# Master.net
KiCad netlist of a schematic drawn in Altium Designer
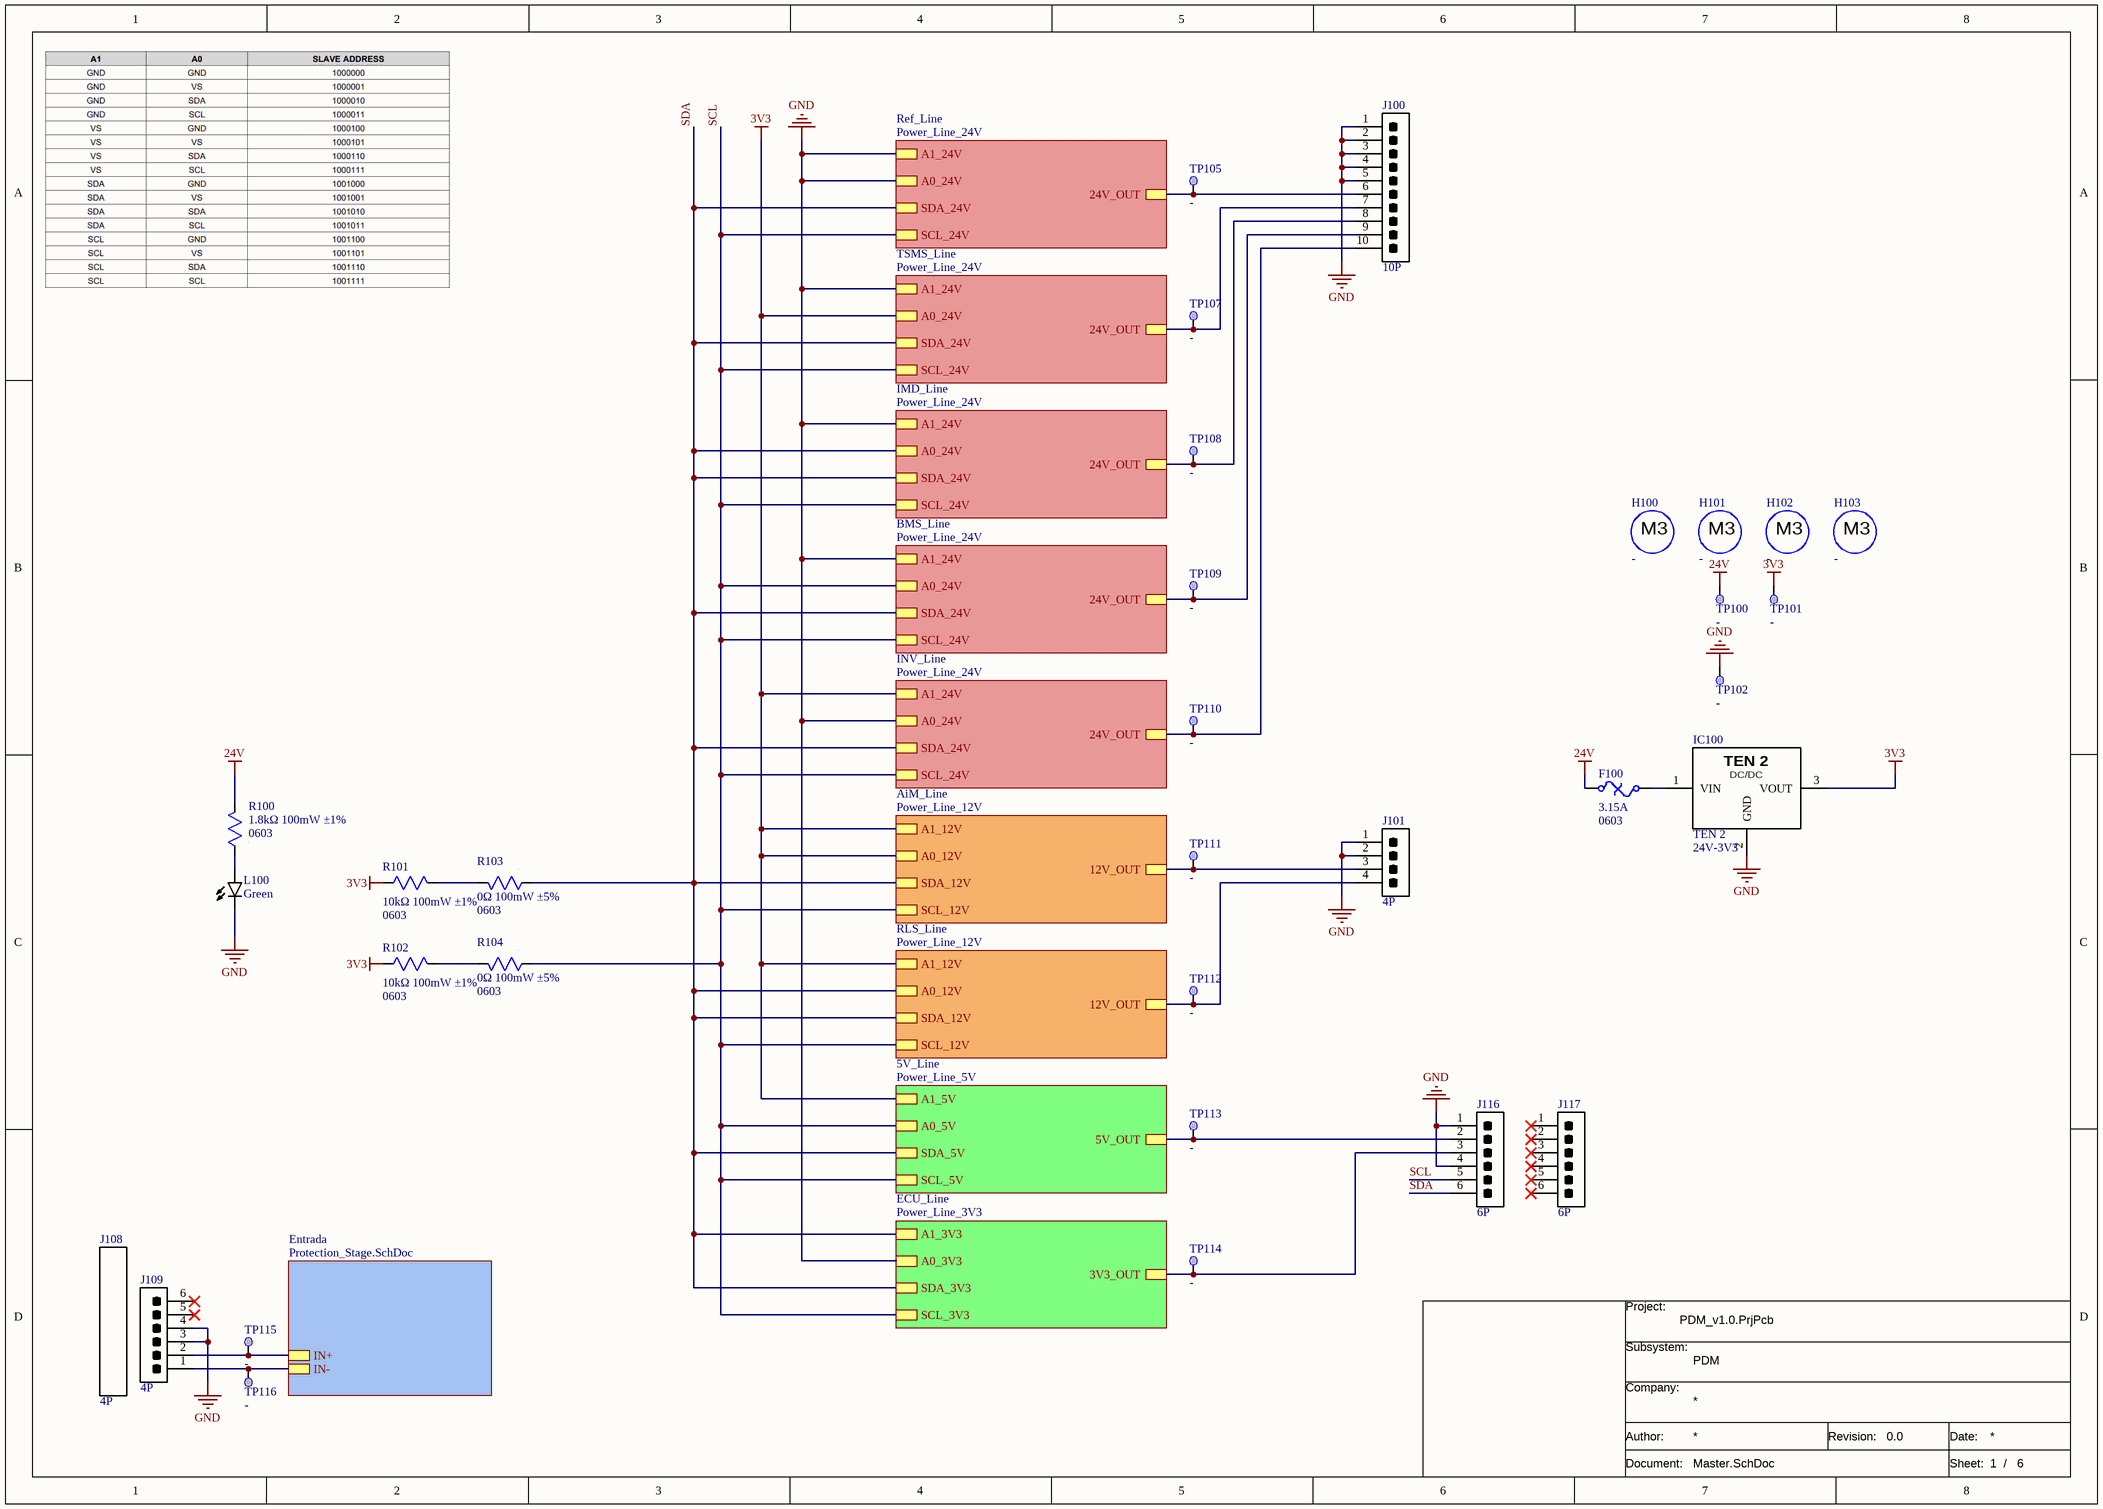
[diagram p0: Master.SchDoc]

(export (version "E")
  (design (tool "Eeschema 10.0.6"))
  (components
    (comp (ref "F100")
      (value "3.15A")
      (footprint "FUSE SMD 0603")
      (description "Surface Mount Fuses 3.15A Slow Blow 0603 SinglFuse")
      (fields
        (field (name "PACKAGE") "0603")
        (field (name "MPN") "SF-0603S315-2")
        (field (name "MANUFACTURER") "Bourns")
      )
      (libsource (lib "eUSR_Database") (part "FUSE"))
    )
    (comp (ref "H100")
      (value "-")
      (footprint "M3")
      (description "M3 Screw")
      (fields (field (name "Comment") "SCREW M3"))
      (libsource (lib "eUSR_Database") (part "SCREW M3"))
    )
    (comp (ref "H101")
      (value "-")
      (footprint "M3")
      (description "M3 Screw")
      (fields (field (name "Comment") "SCREW M3"))
      (libsource (lib "eUSR_Database") (part "SCREW M3"))
    )
    (comp (ref "H102")
      (value "-")
      (footprint "M3")
      (description "M3 Screw")
      (fields (field (name "Comment") "SCREW M3"))
      (libsource (lib "eUSR_Database") (part "SCREW M3"))
    )
    (comp (ref "H103")
      (value "-")
      (footprint "M3")
      (description "M3 Screw")
      (fields (field (name "Comment") "SCREW M3"))
      (libsource (lib "eUSR_Database") (part "SCREW M3"))
    )
    (comp (ref "IC100")
      (value "TEN 2")
      (footprint "TEN 2")
      (description "Convertidores DC/DC para montaje pasante 4.75-36Vin 3.3V 2A switching regulator")
      (fields
        (field (name "ALTIUM_VALUE") "24V-3V3")
        (field (name "MPN") "TSR 2-2433")
        (field (name "MANUFACTURER") "TRACO Power")
      )
      (libsource (lib "eUSR_Database") (part "TEN 2"))
    )
    (comp (ref "J100")
      (value "10P")
      (footprint "657010240101")
      (fields
        (field (name "MPN") "657010240101")
        (field (name "MANUFACTURER") "Wurth Elektronik")
        (field (name "Comment") "CONN 10P")
      )
      (libsource (lib "eUSR_Database") (part "CONN 10P"))
    )
    (comp (ref "J101")
      (value "4P")
      (footprint "657004240101")
      (fields
        (field (name "MPN") "657004240101")
        (field (name "MANUFACTURER") "Wurth Elektronik")
        (field (name "Comment") "CONN 4P")
      )
      (libsource (lib "eUSR_Database") (part "CONN 4P"))
    )
    (comp (ref "J108")
      (value "4P")
      (footprint "657004150201")
      (description "Receptacle Single Row")
      (fields (field (name "MPN") "657004150201") (field (name "MANUFACTURER") "Wurth Elektronik"))
      (libsource (lib "eUSR_Database") (part "AEREO"))
    )
    (comp (ref "J109")
      (value "4P")
      (footprint "657004140101")
      (description "WR-MPC5 Male Header Single Row")
      (fields (field (name "MPN") "657004140101") (field (name "MANUFACTURER") "Wurth Elektronik"))
      (libsource (lib "eUSR_Database") (part "CONN 6P"))
    )
    (comp (ref "J116")
      (value "6P")
      (footprint "HEADERS_MALE_6P_2.54MM")
      (description "Pin Header 6 Position 2.54mm Pitch Single Row Through Hole -55℃~+105℃")
      (fields (field (name "MPN") "2541WV-06P") (field (name "MANUFACTURER") "HanElectricity"))
      (libsource (lib "") (part "CONN 6P_1"))
    )
    (comp (ref "J117")
      (value "6P")
      (footprint "HEADERS_MALE_6P_2.54MM")
      (description "Pin Header 6 Position 2.54mm Pitch Single Row Through Hole -55℃~+105℃")
      (fields (field (name "MPN") "2541WV-06P") (field (name "MANUFACTURER") "HanElectricity"))
      (libsource (lib "") (part "CONN 6P_1"))
    )
    (comp (ref "L100")
      (value "Green")
      (footprint "LED SMD 0603")
      (description "LED de un solo color Green 525nm 1400mcd 2.85V 73deg 0603")
      (fields (field (name "MPN") "VLMTG1400-GS08") (field (name "MANUFACTURER") "Vishay Semiconductors"))
      (libsource (lib "eUSR_Database") (part "LED WHITE"))
    )
    (comp (ref "R100")
      (value "1.8kΩ 100mW ±1%")
      (footprint "RES SMD 0603")
      (description "Resistores de película gruesa - SMD WRIS-RSKS 1.8 kOhms 1 % 0.1 W 0603 AEC-Q200")
      (fields
        (field (name "PACKAGE") "0603")
        (field (name "MPN") "560112116032")
        (field (name "MANUFACTURER") "Wurth Elektronik")
      )
      (libsource (lib "eUSR_Database") (part "RES"))
    )
    (comp (ref "R101")
      (value "10kΩ 100mW ±1%")
      (footprint "RES SMD 0603")
      (description "Resistores de película gruesa - SMD WRIS-RSKS 10 kOhms 1 % 0.1 W 0603 AEC-Q200")
      (fields
        (field (name "PACKAGE") "0603")
        (field (name "MPN") "560112116005")
        (field (name "MANUFACTURER") "Wurth Elektronik")
      )
      (libsource (lib "eUSR_Database") (part "RES"))
    )
    (comp (ref "R102")
      (value "10kΩ 100mW ±1%")
      (footprint "RES SMD 0603")
      (description "Resistores de película gruesa - SMD WRIS-RSKS 10 kOhms 1 % 0.1 W 0603 AEC-Q200")
      (fields
        (field (name "PACKAGE") "0603")
        (field (name "MPN") "560112116005")
        (field (name "MANUFACTURER") "Wurth Elektronik")
      )
      (libsource (lib "eUSR_Database") (part "RES"))
    )
    (comp (ref "R103")
      (value "0Ω 100mW ±5%")
      (footprint "RES SMD 0603")
      (description "Resistores de película gruesa - SMD WRIS-RSKS <0.05 Ohms 0.1 W Jumper 0603 AEC-Q200")
      (fields
        (field (name "PACKAGE") "0603")
        (field (name "MPN") "560112116001")
        (field (name "MANUFACTURER") "Wurth Elektronik")
      )
      (libsource (lib "eUSR_Database") (part "RES"))
    )
    (comp (ref "R104")
      (value "0Ω 100mW ±5%")
      (footprint "RES SMD 0603")
      (description "Resistores de película gruesa - SMD WRIS-RSKS <0.05 Ohms 0.1 W Jumper 0603 AEC-Q200")
      (fields
        (field (name "PACKAGE") "0603")
        (field (name "MPN") "560112116001")
        (field (name "MANUFACTURER") "Wurth Elektronik")
      )
      (libsource (lib "eUSR_Database") (part "RES"))
    )
    (comp (ref "TP100")
      (value "-")
      (footprint "TP_SMD_1MM")
      (description "Test Point")
      (libsource (lib "") (part "TP1mm_1"))
    )
    (comp (ref "TP101")
      (value "-")
      (footprint "TP_SMD_1MM")
      (description "Test Point")
      (libsource (lib "") (part "TP1mm_1"))
    )
    (comp (ref "TP102")
      (value "-")
      (footprint "TP_SMD_1MM")
      (description "Test Point")
      (libsource (lib "") (part "TP1mm_1"))
    )
    (comp (ref "TP105")
      (value "-")
      (footprint "TP_SMD_1MM")
      (description "Test Point")
      (libsource (lib "eUSR_Database") (part "TP1mm"))
    )
    (comp (ref "TP107")
      (value "-")
      (footprint "TP_SMD_1MM")
      (description "Test Point")
      (libsource (lib "eUSR_Database") (part "TP1mm"))
    )
    (comp (ref "TP108")
      (value "-")
      (footprint "TP_SMD_1MM")
      (description "Test Point")
      (libsource (lib "eUSR_Database") (part "TP1mm"))
    )
    (comp (ref "TP109")
      (value "-")
      (footprint "TP_SMD_1MM")
      (description "Test Point")
      (libsource (lib "eUSR_Database") (part "TP1mm"))
    )
    (comp (ref "TP110")
      (value "-")
      (footprint "TP_SMD_1MM")
      (description "Test Point")
      (libsource (lib "eUSR_Database") (part "TP1mm"))
    )
    (comp (ref "TP111")
      (value "-")
      (footprint "TP_SMD_1MM")
      (description "Test Point")
      (libsource (lib "eUSR_Database") (part "TP1mm"))
    )
    (comp (ref "TP112")
      (value "-")
      (footprint "TP_SMD_1MM")
      (description "Test Point")
      (libsource (lib "eUSR_Database") (part "TP1mm"))
    )
    (comp (ref "TP113")
      (value "-")
      (footprint "TP_SMD_1MM")
      (description "Test Point")
      (libsource (lib "eUSR_Database") (part "TP1mm"))
    )
    (comp (ref "TP114")
      (value "-")
      (footprint "TP_SMD_1MM")
      (description "Test Point")
      (libsource (lib "eUSR_Database") (part "TP1mm"))
    )
    (comp (ref "TP115")
      (value "-")
      (footprint "TP_SMD_1MM")
      (description "Test Point")
      (libsource (lib "eUSR_Database") (part "TP1mm"))
    )
    (comp (ref "TP116")
      (value "-")
      (footprint "TP_SMD_1MM")
      (description "Test Point")
      (libsource (lib "") (part "TP1mm_1"))
    )
  )
  (nets
    (net (code "1") (name "/3V3_OUT") (class "Default")
      (node (ref "J116") (pin "3") (pinfunction "3_3") (pintype "passive"))
      (node (ref "TP114") (pin "1") (pinfunction "1_1") (pintype "passive"))
    )
    (net (code "2") (name "/5V_OUT") (class "Default")
      (node (ref "J116") (pin "2") (pinfunction "2_2") (pintype "passive"))
      (node (ref "TP113") (pin "1") (pinfunction "1_1") (pintype "passive"))
    )
    (net (code "3") (name "/12V_OUT") (class "Default")
      (node (ref "J101") (pin "4") (pinfunction "4_4") (pintype "passive"))
      (node (ref "TP112") (pin "1") (pinfunction "1_1") (pintype "passive"))
    )
    (net (code "4") (name "/12V_OUT_1") (class "Default")
      (node (ref "J101") (pin "3") (pinfunction "3_3") (pintype "passive"))
      (node (ref "TP111") (pin "1") (pinfunction "1_1") (pintype "passive"))
    )
    (net (code "5") (name "/24V_OUT") (class "Default")
      (node (ref "J100") (pin "6") (pinfunction "6_6") (pintype "passive"))
      (node (ref "TP105") (pin "1") (pinfunction "1_1") (pintype "passive"))
    )
    (net (code "6") (name "/24V_OUT_1") (class "Default")
      (node (ref "J100") (pin "10") (pinfunction "10_10") (pintype "passive"))
      (node (ref "TP110") (pin "1") (pinfunction "1_1") (pintype "passive"))
    )
    (net (code "7") (name "/24V_OUT_2") (class "Default")
      (node (ref "J100") (pin "9") (pinfunction "9_9") (pintype "passive"))
      (node (ref "TP109") (pin "1") (pinfunction "1_1") (pintype "passive"))
    )
    (net (code "8") (name "/24V_OUT_3") (class "Default")
      (node (ref "J100") (pin "7") (pinfunction "7_7") (pintype "passive"))
      (node (ref "TP107") (pin "1") (pinfunction "1_1") (pintype "passive"))
    )
    (net (code "9") (name "/24V_OUT_4") (class "Default")
      (node (ref "J100") (pin "8") (pinfunction "8_8") (pintype "passive"))
      (node (ref "TP108") (pin "1") (pinfunction "1_1") (pintype "passive"))
    )
    (net (code "10") (name "/IN+") (class "Default")
      (node (ref "J109") (pin "2") (pinfunction "2_2") (pintype "passive"))
      (node (ref "TP115") (pin "1") (pinfunction "1_1") (pintype "passive"))
    )
    (net (code "11") (name "/IN-") (class "Default")
      (node (ref "J109") (pin "1") (pinfunction "1_1") (pintype "passive"))
      (node (ref "TP116") (pin "1") (pinfunction "1_1") (pintype "passive"))
    )
    (net (code "12") (name "/SCL") (class "Default")
      (node (ref "J116") (pin "5") (pinfunction "5_5") (pintype "passive"))
      (node (ref "R104") (pin "1") (pinfunction "1_1") (pintype "passive"))
    )
    (net (code "13") (name "/SDA") (class "Default")
      (node (ref "J116") (pin "6") (pinfunction "6_6") (pintype "passive"))
      (node (ref "R103") (pin "1") (pinfunction "1_1") (pintype "passive"))
    )
    (net (code "14") (name "3V3") (class "Default")
      (node (ref "IC100") (pin "3") (pinfunction "VOUT_3") (pintype "passive"))
      (node (ref "R101") (pin "1") (pinfunction "1_1") (pintype "passive"))
      (node (ref "R102") (pin "1") (pinfunction "1_1") (pintype "passive"))
      (node (ref "TP101") (pin "1") (pinfunction "1_1") (pintype "passive"))
    )
    (net (code "15") (name "24V") (class "Default")
      (node (ref "F100") (pin "1") (pinfunction "1_1") (pintype "passive"))
      (node (ref "R100") (pin "2") (pinfunction "2_2") (pintype "passive"))
      (node (ref "TP100") (pin "1") (pinfunction "1_1") (pintype "passive"))
    )
    (net (code "16") (name "GND") (class "Default")
      (node (ref "IC100") (pin "2") (pinfunction "GND_2") (pintype "passive"))
      (node (ref "J100") (pin "1") (pinfunction "1_1") (pintype "passive"))
      (node (ref "J100") (pin "2") (pinfunction "2_2") (pintype "passive"))
      (node (ref "J100") (pin "3") (pinfunction "3_3") (pintype "passive"))
      (node (ref "J100") (pin "4") (pinfunction "4_4") (pintype "passive"))
      (node (ref "J100") (pin "5") (pinfunction "5_5") (pintype "passive"))
      (node (ref "J101") (pin "1") (pinfunction "1_1") (pintype "passive"))
      (node (ref "J101") (pin "2") (pinfunction "2_2") (pintype "passive"))
      (node (ref "J109") (pin "3") (pinfunction "3_3") (pintype "passive"))
      (node (ref "J109") (pin "4") (pinfunction "4_4") (pintype "passive"))
      (node (ref "J116") (pin "1") (pinfunction "1_1") (pintype "passive"))
      (node (ref "J116") (pin "4") (pinfunction "4_4") (pintype "passive"))
      (node (ref "L100") (pin "C") (pinfunction "C_C") (pintype "passive"))
      (node (ref "TP102") (pin "1") (pinfunction "1_1") (pintype "passive"))
    )
    (net (code "17") (name "Net-(IC100-VIN)") (class "Default")
      (node (ref "F100") (pin "2") (pinfunction "2_2") (pintype "passive"))
      (node (ref "IC100") (pin "1") (pinfunction "VIN_1") (pintype "passive"))
    )
    (net (code "18") (name "Net-(L100-PadA)") (class "Default")
      (node (ref "L100") (pin "A") (pinfunction "A_A") (pintype "passive"))
      (node (ref "R100") (pin "1") (pinfunction "1_1") (pintype "passive"))
    )
    (net (code "19") (name "Net-(R101-Pad2)") (class "Default")
      (node (ref "R101") (pin "2") (pinfunction "2_2") (pintype "passive"))
      (node (ref "R103") (pin "2") (pinfunction "2_2") (pintype "passive"))
    )
    (net (code "20") (name "Net-(R102-Pad2)") (class "Default")
      (node (ref "R102") (pin "2") (pinfunction "2_2") (pintype "passive"))
      (node (ref "R104") (pin "2") (pinfunction "2_2") (pintype "passive"))
    )
    (net (code "21") (name "unconnected-(J109-Pad5)") (class "Default")
      (node (ref "J109") (pin "5") (pinfunction "5_5") (pintype "passive+no_connect"))
    )
    (net (code "22") (name "unconnected-(J109-Pad6)") (class "Default")
      (node (ref "J109") (pin "6") (pinfunction "6_6") (pintype "passive+no_connect"))
    )
    (net (code "23") (name "unconnected-(J117-Pad1)") (class "Default")
      (node (ref "J117") (pin "1") (pinfunction "1_1") (pintype "passive+no_connect"))
    )
    (net (code "24") (name "unconnected-(J117-Pad2)") (class "Default")
      (node (ref "J117") (pin "2") (pinfunction "2_2") (pintype "passive+no_connect"))
    )
    (net (code "25") (name "unconnected-(J117-Pad3)") (class "Default")
      (node (ref "J117") (pin "3") (pinfunction "3_3") (pintype "passive+no_connect"))
    )
    (net (code "26") (name "unconnected-(J117-Pad4)") (class "Default")
      (node (ref "J117") (pin "4") (pinfunction "4_4") (pintype "passive+no_connect"))
    )
    (net (code "27") (name "unconnected-(J117-Pad5)") (class "Default")
      (node (ref "J117") (pin "5") (pinfunction "5_5") (pintype "passive+no_connect"))
    )
    (net (code "28") (name "unconnected-(J117-Pad6)") (class "Default")
      (node (ref "J117") (pin "6") (pinfunction "6_6") (pintype "passive+no_connect"))
    )
  )
)
